# LedDimming.net
KiCad netlist of a schematic drawn in Altium Designer
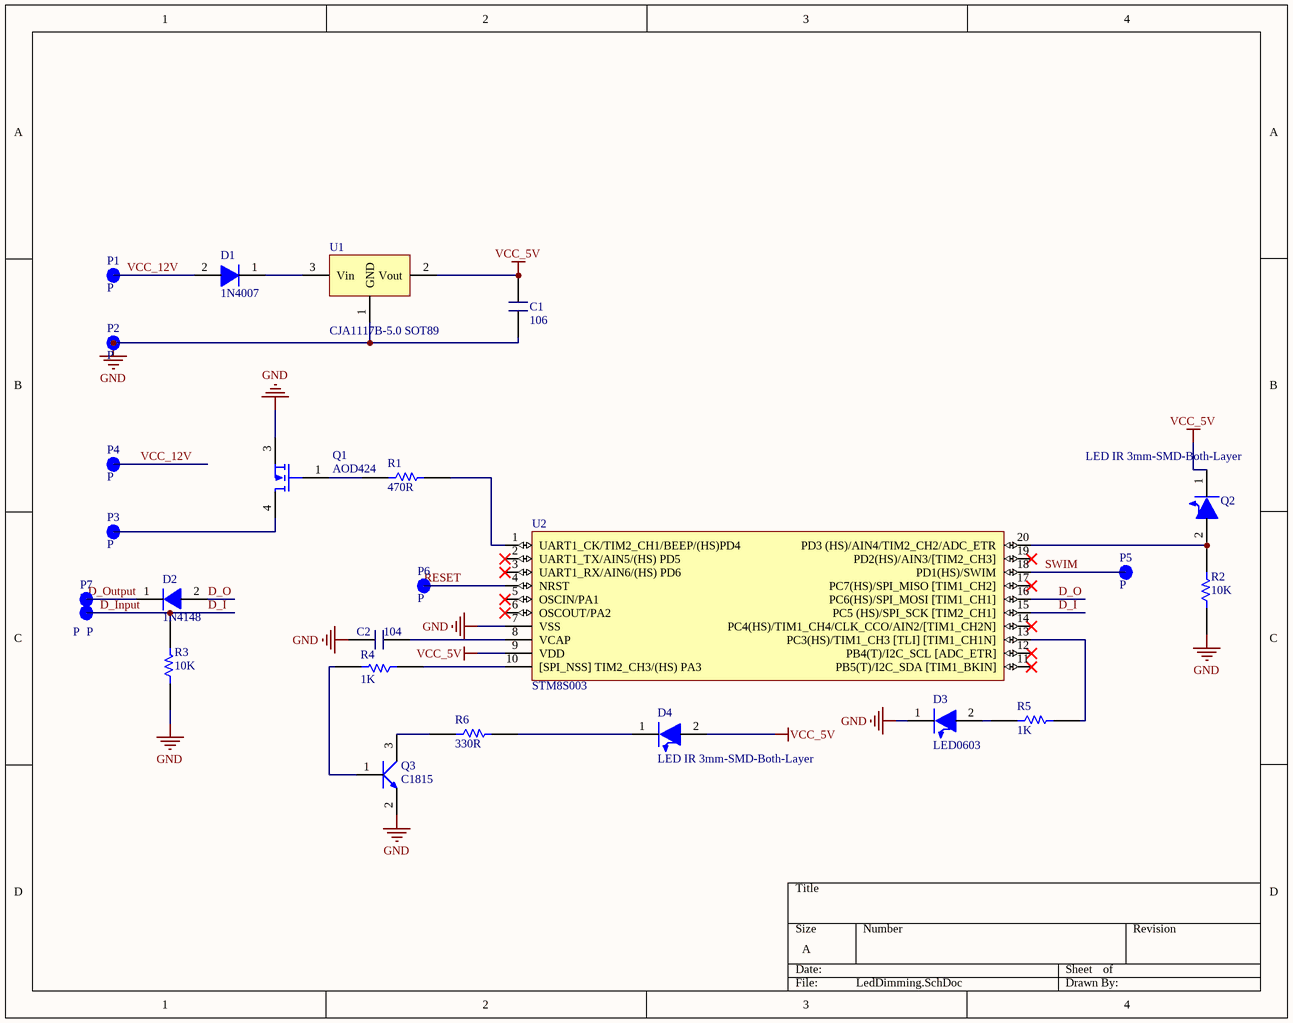
[diagram p0: LedDimming.SchDoc]

(export (version "E")
  (design (tool "Eeschema 10.0.6"))
  (components
    (comp (ref "C1")
      (value "106")
      (footprint "CAPC2012X12N")
      (libsource (lib "Integrated_Library1") (part "Capacitor 106"))
    )
    (comp (ref "C2")
      (value "104")
      (footprint "CAPC2012X12N")
      (libsource (lib "Integrated_Library1") (part "Capacitor 104 0603"))
    )
    (comp (ref "D1")
      (value "1N4007")
      (footprint "SODFL504X244-2N")
      (description "1N4007_SMD")
      (libsource (lib "Integrated_Library1") (part "1N4007_SMD Diode"))
    )
    (comp (ref "D2")
      (value "1N4148")
      (footprint "DIOMELF3515N")
      (description "DIODE GEN PURP 75V 200MA DO213AA")
      (libsource (lib "Integrated_Library1") (part "1N4148_SMD"))
    )
    (comp (ref "D3")
      (value "LED0603")
      (footprint "DIOC1608X06N")
      (libsource (lib "Integrated_Library1") (part "LED0603"))
    )
    (comp (ref "D4")
      (value "LED IR 3mm-SMD-Both-Layer")
      (footprint "LED_IR_3mm-SMD-Both_Layer")
      (libsource (lib "Integrated_Library1") (part "LED IR 3mm-SMD-Both-Layer"))
    )
    (comp (ref "P1") (value "P") (footprint "Point") (libsource (lib "Integrated_Library1") (part "Point")))
    (comp (ref "P2") (value "P") (footprint "Point") (libsource (lib "Integrated_Library1") (part "Point")))
    (comp (ref "P3") (value "P") (footprint "Point") (libsource (lib "Integrated_Library1") (part "Point")))
    (comp (ref "P4") (value "P") (footprint "Point") (libsource (lib "Integrated_Library1") (part "Point")))
    (comp (ref "P5") (value "P") (footprint "Point") (libsource (lib "Integrated_Library1") (part "Point")))
    (comp (ref "P6") (value "P") (footprint "Point") (libsource (lib "Integrated_Library1") (part "Point")))
    (comp (ref "P7") (value "P") (footprint "Point") (libsource (lib "Integrated_Library1") (part "Point")))
    (comp (ref "P8") (value "P") (footprint "Point") (libsource (lib "Integrated_Library1") (part "Point")))
    (comp (ref "Q1")
      (value "AOD424")
      (footprint "DPAK228P991X229-3N_TO252")
      (description "AOD424 20V N-Channel MOSFET")
      (libsource (lib "Integrated_Library1") (part "AOD424 20V N-Channel MOSFET"))
    )
    (comp (ref "Q2")
      (value "LED IR 3mm-SMD-Both-Layer")
      (footprint "LED_IR_3mm-SMD-Both_Layer")
      (libsource (lib "Integrated_Library1") (part "LED IR 3mm-SMD-Both-Layer"))
    )
    (comp (ref "Q3")
      (value "C1815")
      (footprint "SOT95P278X125-3N")
      (description "SOT-23 Plastic-Encapsulate Transistors")
      (libsource (lib "Integrated_Library1") (part "Transitor C1815 NPN"))
    )
    (comp (ref "R1")
      (value "470R")
      (footprint "RESC2608X06N_0603")
      (description "Thick Film Resistors - SMD 470 ohm 5%")
      (libsource (lib "Integrated_Library1") (part "R470_0603_5%"))
    )
    (comp (ref "R2")
      (value "10K")
      (footprint "RESC2608X06N_0603")
      (description "RES SMD 10K OHM 1% 1/4W 0603")
      (libsource (lib "Integrated_Library1") (part "R10k_0603_5%"))
    )
    (comp (ref "R3")
      (value "10K")
      (footprint "RESC2608X06N_0603")
      (description "RES SMD 10K OHM 1% 1/4W 0603")
      (libsource (lib "Integrated_Library1") (part "R10k_0603_5%"))
    )
    (comp (ref "R4")
      (value "1K")
      (footprint "RESC2608X06N_0603")
      (description "Thick Film Resistors - SMD 0603 1kOHMS 5% 1/10WATT")
      (libsource (lib "Integrated_Library1") (part "1k_0603_5%"))
    )
    (comp (ref "R5")
      (value "1K")
      (footprint "RESC2608X06N_0603")
      (description "Thick Film Resistors - SMD 0603 1kOHMS 5% 1/10WATT")
      (libsource (lib "Integrated_Library1") (part "1k_0603_5%"))
    )
    (comp (ref "R6")
      (value "330R")
      (footprint "RESC2608X06N_0603")
      (description "Thick Film Resistors - SMD 330 ohm 5%")
      (libsource (lib "Integrated_Library1") (part "R330_0603_5%"))
    )
    (comp (ref "U1")
      (value "CJA1117B-5.0 SOT89")
      (footprint "SOT89-150P409X160-3N")
      (description "CJA1117B-5.0 SOT89 Power IC 1A 5V_IC")
      (libsource (lib "Integrated_Library1") (part "CJA1117B-5.0 SOT89"))
    )
    (comp (ref "U2")
      (value "STM8S003")
      (footprint "TSOP65P640X120-20N")
      (description "MCU 8-bit STM8S STM8 CISC 8KB Flash 3.3V/5V 20-Pin TSSOP T/R")
      (libsource (lib "Integrated_Library1") (part "STM8S003"))
    )
  )
  (nets
    (net (code "1") (name "/D_I") (class "Default")
      (node (ref "P8") (pin "1") (pinfunction "1_1") (pintype "passive"))
      (node (ref "R3") (pin "2") (pinfunction "2_2") (pintype "passive"))
      (node (ref "U2") (pin "15") (pinfunction "PC5_(HS)/SPI_SCK_[TIM2_CH1]_15") (pintype "bidirectional"))
    )
    (net (code "2") (name "/D_O") (class "Default")
      (node (ref "D2") (pin "2") (pinfunction "A_2") (pintype "passive"))
      (node (ref "U2") (pin "16") (pinfunction "PC6(HS)/SPI_MOSI_[TIM1_CH1]_16") (pintype "bidirectional"))
    )
    (net (code "3") (name "/D_Output") (class "Default")
      (node (ref "D2") (pin "1") (pinfunction "C_1") (pintype "passive"))
      (node (ref "P7") (pin "1") (pinfunction "1_1") (pintype "passive"))
    )
    (net (code "4") (name "/RESET") (class "Default")
      (node (ref "P6") (pin "1") (pinfunction "1_1") (pintype "passive"))
      (node (ref "U2") (pin "4") (pinfunction "NRST_4") (pintype "bidirectional"))
    )
    (net (code "5") (name "/SWIM") (class "Default")
      (node (ref "P5") (pin "1") (pinfunction "1_1") (pintype "passive"))
      (node (ref "U2") (pin "18") (pinfunction "PD1(HS)/SWIM_18") (pintype "bidirectional"))
    )
    (net (code "6") (name "/VCC_12V") (class "Default")
      (node (ref "D1") (pin "2") (pinfunction "A_2") (pintype "passive"))
      (node (ref "P1") (pin "1") (pinfunction "1_1") (pintype "passive"))
      (node (ref "P4") (pin "1") (pinfunction "1_1") (pintype "passive"))
    )
    (net (code "7") (name "GND") (class "Default")
      (node (ref "C1") (pin "1") (pinfunction "1_1") (pintype "passive"))
      (node (ref "C2") (pin "1") (pinfunction "1_1") (pintype "passive"))
      (node (ref "D3") (pin "1") (pinfunction "A_1") (pintype "passive"))
      (node (ref "P2") (pin "1") (pinfunction "1_1") (pintype "passive"))
      (node (ref "Q1") (pin "3") (pinfunction "S_3") (pintype "passive"))
      (node (ref "Q3") (pin "2") (pinfunction "E_2") (pintype "passive"))
      (node (ref "R2") (pin "1") (pinfunction "1_1") (pintype "passive"))
      (node (ref "R3") (pin "1") (pinfunction "1_1") (pintype "passive"))
      (node (ref "U1") (pin "1") (pinfunction "GND_1") (pintype "power_in"))
      (node (ref "U2") (pin "7") (pinfunction "VSS_7") (pintype "power_in"))
    )
    (net (code "8") (name "Net-(D1-C)") (class "Default")
      (node (ref "D1") (pin "1") (pinfunction "C_1") (pintype "passive"))
      (node (ref "U1") (pin "3") (pinfunction "Vin_3") (pintype "power_in"))
    )
    (net (code "9") (name "Net-(D3-C)") (class "Default")
      (node (ref "D3") (pin "2") (pinfunction "C_2") (pintype "passive"))
      (node (ref "R5") (pin "1") (pinfunction "1_1") (pintype "passive"))
    )
    (net (code "10") (name "Net-(D4-A)") (class "Default")
      (node (ref "D4") (pin "1") (pinfunction "A_1") (pintype "passive"))
      (node (ref "R6") (pin "2") (pinfunction "2_2") (pintype "passive"))
    )
    (net (code "11") (name "Net-(Q1-D)") (class "Default")
      (node (ref "P3") (pin "1") (pinfunction "1_1") (pintype "passive"))
      (node (ref "Q1") (pin "4") (pinfunction "D_4") (pintype "passive"))
    )
    (net (code "12") (name "Net-(Q1-G)") (class "Default")
      (node (ref "Q1") (pin "1") (pinfunction "G_1") (pintype "passive"))
      (node (ref "R1") (pin "1") (pinfunction "1_1") (pintype "passive"))
    )
    (net (code "13") (name "Net-(Q2-C)") (class "Default")
      (node (ref "Q2") (pin "2") (pinfunction "C_2") (pintype "passive"))
      (node (ref "R2") (pin "2") (pinfunction "2_2") (pintype "passive"))
      (node (ref "U2") (pin "20") (pinfunction "PD3_(HS)/AIN4/TIM2_CH2/ADC_ETR_20") (pintype "bidirectional"))
    )
    (net (code "14") (name "Net-(Q3-B)") (class "Default")
      (node (ref "Q3") (pin "1") (pinfunction "B_1") (pintype "passive"))
      (node (ref "R4") (pin "2") (pinfunction "2_2") (pintype "passive"))
    )
    (net (code "15") (name "Net-(Q3-C)") (class "Default")
      (node (ref "Q3") (pin "3") (pinfunction "C_3") (pintype "passive"))
      (node (ref "R6") (pin "1") (pinfunction "1_1") (pintype "passive"))
    )
    (net (code "16") (name "Net-(U2-PC3(HS){slash}TIM1_CH3_[TLI]_[TIM1_CH1N])") (class "Default")
      (node (ref "R5") (pin "2") (pinfunction "2_2") (pintype "passive"))
      (node (ref "U2") (pin "13") (pinfunction "PC3(HS)/TIM1_CH3_[TLI]_[TIM1_CH1N]_13") (pintype "bidirectional"))
    )
    (net (code "17") (name "Net-(U2-UART1_CK{slash}TIM2_CH1{slash}BEEP{slash}(HS)PD4)") (class "Default")
      (node (ref "R1") (pin "2") (pinfunction "2_2") (pintype "passive"))
      (node (ref "U2") (pin "1") (pinfunction "UART1_CK/TIM2_CH1/BEEP/(HS)PD4_1") (pintype "bidirectional"))
    )
    (net (code "18") (name "Net-(U2-VCAP)") (class "Default")
      (node (ref "C2") (pin "2") (pinfunction "2_2") (pintype "passive"))
      (node (ref "U2") (pin "8") (pinfunction "VCAP_8") (pintype "power_in"))
    )
    (net (code "19") (name "Net-(U2-[SPI_NSS]_TIM2_CH3{slash}(HS)_PA3)") (class "Default")
      (node (ref "R4") (pin "1") (pinfunction "1_1") (pintype "passive"))
      (node (ref "U2") (pin "10") (pinfunction "[SPI_NSS]_TIM2_CH3/(HS)_PA3_10") (pintype "power_in"))
    )
    (net (code "20") (name "VCC_5V") (class "Default")
      (node (ref "C1") (pin "2") (pinfunction "2_2") (pintype "passive"))
      (node (ref "D4") (pin "2") (pinfunction "C_2") (pintype "passive"))
      (node (ref "Q2") (pin "1") (pinfunction "A_1") (pintype "passive"))
      (node (ref "U1") (pin "2") (pinfunction "Vout_2") (pintype "power_in"))
      (node (ref "U2") (pin "9") (pinfunction "VDD_9") (pintype "power_in"))
    )
    (net (code "21") (name "unconnected-(U2-OSCIN{slash}PA1-Pad5)") (class "Default")
      (node (ref "U2") (pin "5") (pinfunction "OSCIN/PA1_5") (pintype "bidirectional+no_connect"))
    )
    (net (code "22") (name "unconnected-(U2-OSCOUT{slash}PA2-Pad6)") (class "Default")
      (node (ref "U2") (pin "6") (pinfunction "OSCOUT/PA2_6") (pintype "bidirectional+no_connect"))
    )
    (net (code "23") (name "unconnected-(U2-PB4(T){slash}I2C_SCL_[ADC_ETR]-Pad12)") (class "Default")
      (node (ref "U2") (pin "12") (pinfunction "PB4(T)/I2C_SCL_[ADC_ETR]_12") (pintype "bidirectional+no_connect"))
    )
    (net (code "24") (name "unconnected-(U2-PB5(T){slash}I2C_SDA_[TIM1_BKIN]-Pad11)") (class "Default")
      (node (ref "U2") (pin "11") (pinfunction "PB5(T)/I2C_SDA_[TIM1_BKIN]_11") (pintype "bidirectional+no_connect"))
    )
    (net (code "25") (name "unconnected-(U2-PC4(HS){slash}TIM1_CH4{slash}CLK_CCO{slash}AIN2{slash}[TIM1_CH2N]-Pad14)") (class "Default")
      (node (ref "U2") (pin "14") (pinfunction "PC4(HS)/TIM1_CH4/CLK_CCO/AIN2/[TIM1_CH2N]_14") (pintype "bidirectional+no_connect"))
    )
    (net (code "26") (name "unconnected-(U2-PC7(HS){slash}SPI_MISO_[TIM1_CH2]-Pad17)") (class "Default")
      (node (ref "U2") (pin "17") (pinfunction "PC7(HS)/SPI_MISO_[TIM1_CH2]_17") (pintype "bidirectional+no_connect"))
    )
    (net (code "27") (name "unconnected-(U2-PD2(HS){slash}AIN3{slash}[TIM2_CH3]-Pad19)") (class "Default")
      (node (ref "U2") (pin "19") (pinfunction "PD2(HS)/AIN3/[TIM2_CH3]_19") (pintype "bidirectional+no_connect"))
    )
    (net (code "28") (name "unconnected-(U2-UART1_RX{slash}AIN6{slash}(HS)_PD6-Pad3)") (class "Default")
      (node (ref "U2") (pin "3") (pinfunction "UART1_RX/AIN6/(HS)_PD6_3") (pintype "bidirectional+no_connect"))
    )
    (net (code "29") (name "unconnected-(U2-UART1_TX{slash}AIN5{slash}(HS)_PD5-Pad2)") (class "Default")
      (node (ref "U2") (pin "2") (pinfunction "UART1_TX/AIN5/(HS)_PD5_2") (pintype "bidirectional+no_connect"))
    )
  )
)
